# switch_1.net
KiCad netlist of a schematic drawn in Altium Designer
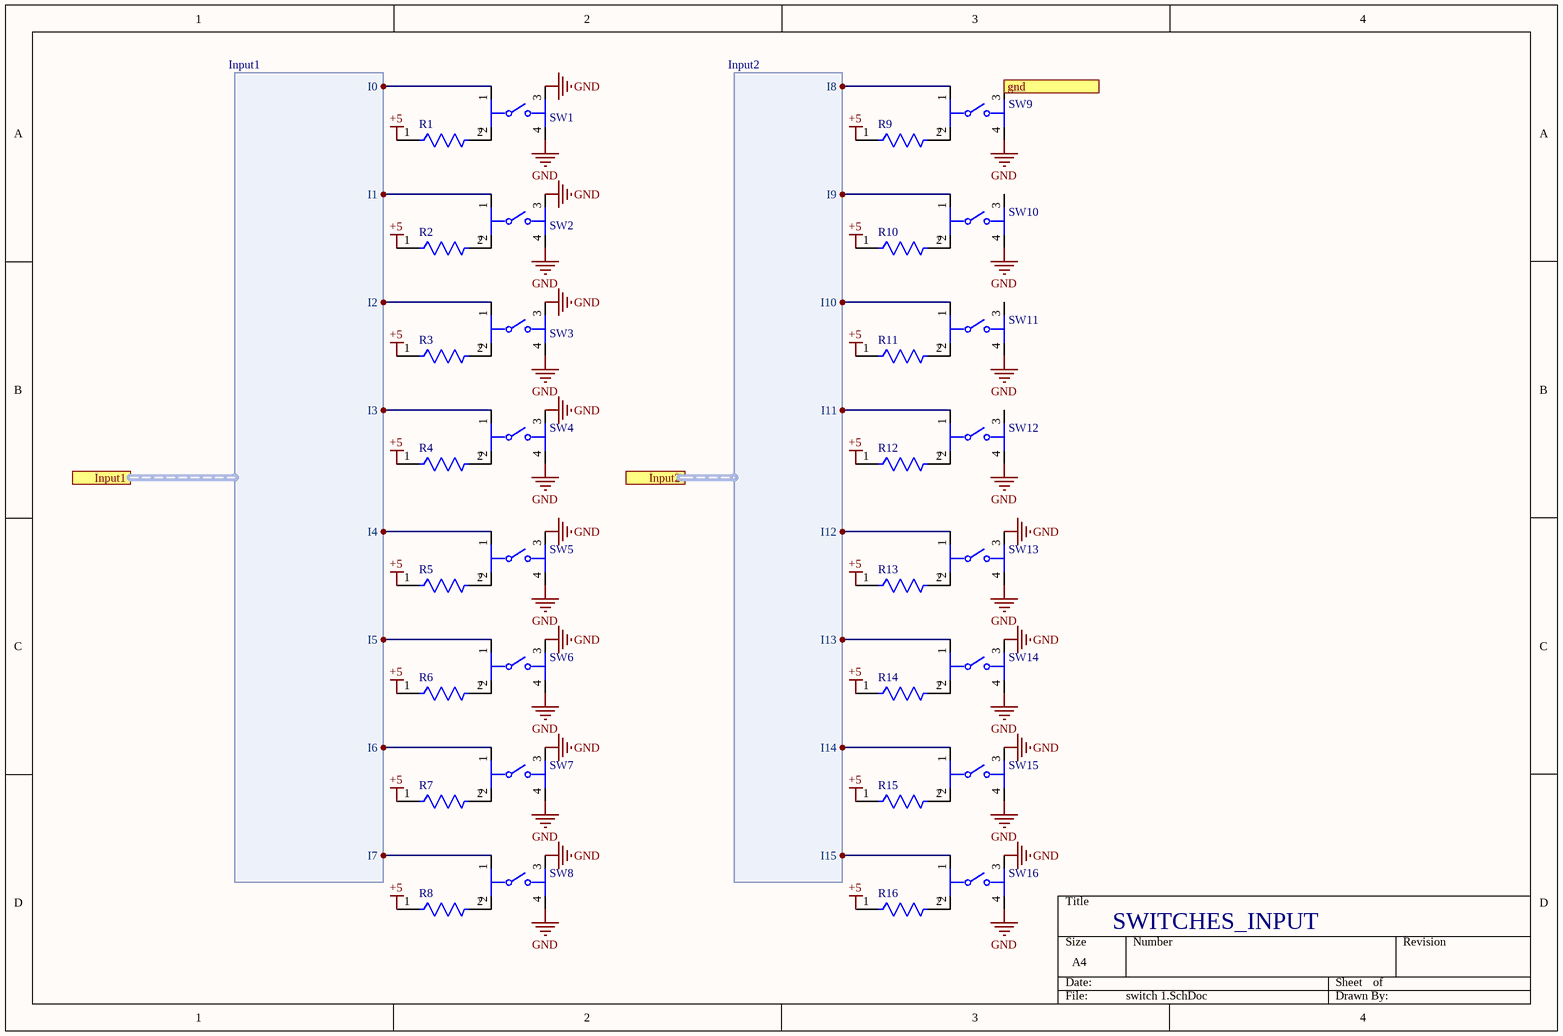
[diagram p0: switch 1.SchDoc]

(export (version "E")
  (design (tool "Eeschema 10.0.6"))
  (components
    (comp (ref "R1")
      (value "MRS25000C1001FCT00")
      (footprint "FP-MRS25-MFG")
      (description "RES 1K OHM 0.6W 1% AXIAL")
      (fields (field (name "TOLERANCE") "1%"))
      (libsource (lib "Altium Content Vault") (part "1029c3af85768c4190bb7ad29bc67b5"))
    )
    (comp (ref "R2")
      (value "MRS25000C1001FCT00")
      (footprint "FP-MRS25-MFG")
      (description "RES 1K OHM 0.6W 1% AXIAL")
      (fields (field (name "TOLERANCE") "1%"))
      (libsource (lib "Altium Content Vault") (part "1029c3af85768c4190bb7ad29bc67b5"))
    )
    (comp (ref "R3")
      (value "MRS25000C1001FCT00")
      (footprint "FP-MRS25-MFG")
      (description "RES 1K OHM 0.6W 1% AXIAL")
      (fields (field (name "TOLERANCE") "1%"))
      (libsource (lib "Altium Content Vault") (part "1029c3af85768c4190bb7ad29bc67b5"))
    )
    (comp (ref "R4")
      (value "MRS25000C1001FCT00")
      (footprint "FP-MRS25-MFG")
      (description "RES 1K OHM 0.6W 1% AXIAL")
      (fields (field (name "TOLERANCE") "1%"))
      (libsource (lib "Altium Content Vault") (part "1029c3af85768c4190bb7ad29bc67b5"))
    )
    (comp (ref "R5")
      (value "MRS25000C1001FCT00")
      (footprint "FP-MRS25-MFG")
      (description "RES 1K OHM 0.6W 1% AXIAL")
      (fields (field (name "TOLERANCE") "1%"))
      (libsource (lib "Altium Content Vault") (part "1029c3af85768c4190bb7ad29bc67b5"))
    )
    (comp (ref "R6")
      (value "MRS25000C1001FCT00")
      (footprint "FP-MRS25-MFG")
      (description "RES 1K OHM 0.6W 1% AXIAL")
      (fields (field (name "TOLERANCE") "1%"))
      (libsource (lib "Altium Content Vault") (part "1029c3af85768c4190bb7ad29bc67b5"))
    )
    (comp (ref "R7")
      (value "MRS25000C1001FCT00")
      (footprint "FP-MRS25-MFG")
      (description "RES 1K OHM 0.6W 1% AXIAL")
      (fields (field (name "TOLERANCE") "1%"))
      (libsource (lib "Altium Content Vault") (part "1029c3af85768c4190bb7ad29bc67b5"))
    )
    (comp (ref "R8")
      (value "MRS25000C1001FCT00")
      (footprint "FP-MRS25-MFG")
      (description "RES 1K OHM 0.6W 1% AXIAL")
      (fields (field (name "TOLERANCE") "1%"))
      (libsource (lib "Altium Content Vault") (part "1029c3af85768c4190bb7ad29bc67b5"))
    )
    (comp (ref "R9")
      (value "MRS25000C1001FCT00")
      (footprint "FP-MRS25-MFG")
      (description "RES 1K OHM 0.6W 1% AXIAL")
      (fields (field (name "TOLERANCE") "1%"))
      (libsource (lib "Altium Content Vault") (part "1029c3af85768c4190bb7ad29bc67b5"))
    )
    (comp (ref "R10")
      (value "MRS25000C1001FCT00")
      (footprint "FP-MRS25-MFG")
      (description "RES 1K OHM 0.6W 1% AXIAL")
      (fields (field (name "TOLERANCE") "1%"))
      (libsource (lib "Altium Content Vault") (part "1029c3af85768c4190bb7ad29bc67b5"))
    )
    (comp (ref "R11")
      (value "MRS25000C1001FCT00")
      (footprint "FP-MRS25-MFG")
      (description "RES 1K OHM 0.6W 1% AXIAL")
      (fields (field (name "TOLERANCE") "1%"))
      (libsource (lib "Altium Content Vault") (part "1029c3af85768c4190bb7ad29bc67b5"))
    )
    (comp (ref "R12")
      (value "MRS25000C1001FCT00")
      (footprint "FP-MRS25-MFG")
      (description "RES 1K OHM 0.6W 1% AXIAL")
      (fields (field (name "TOLERANCE") "1%"))
      (libsource (lib "Altium Content Vault") (part "1029c3af85768c4190bb7ad29bc67b5"))
    )
    (comp (ref "R13")
      (value "MRS25000C1001FCT00")
      (footprint "FP-MRS25-MFG")
      (description "RES 1K OHM 0.6W 1% AXIAL")
      (fields (field (name "TOLERANCE") "1%"))
      (libsource (lib "Altium Content Vault") (part "1029c3af85768c4190bb7ad29bc67b5"))
    )
    (comp (ref "R14")
      (value "MRS25000C1001FCT00")
      (footprint "FP-MRS25-MFG")
      (description "RES 1K OHM 0.6W 1% AXIAL")
      (fields (field (name "TOLERANCE") "1%"))
      (libsource (lib "Altium Content Vault") (part "1029c3af85768c4190bb7ad29bc67b5"))
    )
    (comp (ref "R15")
      (value "MRS25000C1001FCT00")
      (footprint "FP-MRS25-MFG")
      (description "RES 1K OHM 0.6W 1% AXIAL")
      (fields (field (name "TOLERANCE") "1%"))
      (libsource (lib "Altium Content Vault") (part "1029c3af85768c4190bb7ad29bc67b5"))
    )
    (comp (ref "R16")
      (value "MRS25000C1001FCT00")
      (footprint "FP-MRS25-MFG")
      (description "RES 1K OHM 0.6W 1% AXIAL")
      (fields (field (name "TOLERANCE") "1%"))
      (libsource (lib "Altium Content Vault") (part "1029c3af85768c4190bb7ad29bc67b5"))
    )
    (comp (ref "SW1")
      (value "1-1825910-5")
      (footprint "FP-1-1825910-5-MFG")
      (description "SWITCH TACTILE SPST-NO 0.05A 24V")
      (libsource (lib "Altium Content Vault") (part "b8895f3f4cefb76e1819d2863dba89b"))
    )
    (comp (ref "SW2")
      (value "1-1825910-5")
      (footprint "FP-1-1825910-5-MFG")
      (description "SWITCH TACTILE SPST-NO 0.05A 24V")
      (libsource (lib "Altium Content Vault") (part "b8895f3f4cefb76e1819d2863dba89b"))
    )
    (comp (ref "SW3")
      (value "1-1825910-5")
      (footprint "FP-1-1825910-5-MFG")
      (description "SWITCH TACTILE SPST-NO 0.05A 24V")
      (libsource (lib "Altium Content Vault") (part "b8895f3f4cefb76e1819d2863dba89b"))
    )
    (comp (ref "SW4")
      (value "1-1825910-5")
      (footprint "FP-1-1825910-5-MFG")
      (description "SWITCH TACTILE SPST-NO 0.05A 24V")
      (libsource (lib "Altium Content Vault") (part "b8895f3f4cefb76e1819d2863dba89b"))
    )
    (comp (ref "SW5")
      (value "1-1825910-5")
      (footprint "FP-1-1825910-5-MFG")
      (description "SWITCH TACTILE SPST-NO 0.05A 24V")
      (libsource (lib "Altium Content Vault") (part "b8895f3f4cefb76e1819d2863dba89b"))
    )
    (comp (ref "SW6")
      (value "1-1825910-5")
      (footprint "FP-1-1825910-5-MFG")
      (description "SWITCH TACTILE SPST-NO 0.05A 24V")
      (libsource (lib "Altium Content Vault") (part "b8895f3f4cefb76e1819d2863dba89b"))
    )
    (comp (ref "SW7")
      (value "1-1825910-5")
      (footprint "FP-1-1825910-5-MFG")
      (description "SWITCH TACTILE SPST-NO 0.05A 24V")
      (libsource (lib "Altium Content Vault") (part "b8895f3f4cefb76e1819d2863dba89b"))
    )
    (comp (ref "SW8")
      (value "1-1825910-5")
      (footprint "FP-1-1825910-5-MFG")
      (description "SWITCH TACTILE SPST-NO 0.05A 24V")
      (libsource (lib "Altium Content Vault") (part "b8895f3f4cefb76e1819d2863dba89b"))
    )
    (comp (ref "SW9")
      (value "1-1825910-5")
      (footprint "FP-1-1825910-5-MFG")
      (description "SWITCH TACTILE SPST-NO 0.05A 24V")
      (libsource (lib "Altium Content Vault") (part "b8895f3f4cefb76e1819d2863dba89b"))
    )
    (comp (ref "SW10")
      (value "1-1825910-5")
      (footprint "FP-1-1825910-5-MFG")
      (description "SWITCH TACTILE SPST-NO 0.05A 24V")
      (libsource (lib "Altium Content Vault") (part "b8895f3f4cefb76e1819d2863dba89b"))
    )
    (comp (ref "SW11")
      (value "1-1825910-5")
      (footprint "FP-1-1825910-5-MFG")
      (description "SWITCH TACTILE SPST-NO 0.05A 24V")
      (libsource (lib "Altium Content Vault") (part "b8895f3f4cefb76e1819d2863dba89b"))
    )
    (comp (ref "SW12")
      (value "1-1825910-5")
      (footprint "FP-1-1825910-5-MFG")
      (description "SWITCH TACTILE SPST-NO 0.05A 24V")
      (libsource (lib "Altium Content Vault") (part "b8895f3f4cefb76e1819d2863dba89b"))
    )
    (comp (ref "SW13")
      (value "1-1825910-5")
      (footprint "FP-1-1825910-5-MFG")
      (description "SWITCH TACTILE SPST-NO 0.05A 24V")
      (libsource (lib "Altium Content Vault") (part "b8895f3f4cefb76e1819d2863dba89b"))
    )
    (comp (ref "SW14")
      (value "1-1825910-5")
      (footprint "FP-1-1825910-5-MFG")
      (description "SWITCH TACTILE SPST-NO 0.05A 24V")
      (libsource (lib "Altium Content Vault") (part "b8895f3f4cefb76e1819d2863dba89b"))
    )
    (comp (ref "SW15")
      (value "1-1825910-5")
      (footprint "FP-1-1825910-5-MFG")
      (description "SWITCH TACTILE SPST-NO 0.05A 24V")
      (libsource (lib "Altium Content Vault") (part "b8895f3f4cefb76e1819d2863dba89b"))
    )
    (comp (ref "SW16")
      (value "1-1825910-5")
      (footprint "FP-1-1825910-5-MFG")
      (description "SWITCH TACTILE SPST-NO 0.05A 24V")
      (libsource (lib "Altium Content Vault") (part "b8895f3f4cefb76e1819d2863dba89b"))
    )
  )
  (nets
    (net (code "3") (name "+5") (class "Default")
      (node (ref "R1") (pin "1") (pinfunction "1_1") (pintype "passive"))
      (node (ref "R10") (pin "1") (pinfunction "1_1") (pintype "passive"))
      (node (ref "R11") (pin "1") (pinfunction "1_1") (pintype "passive"))
      (node (ref "R12") (pin "1") (pinfunction "1_1") (pintype "passive"))
      (node (ref "R13") (pin "1") (pinfunction "1_1") (pintype "passive"))
      (node (ref "R14") (pin "1") (pinfunction "1_1") (pintype "passive"))
      (node (ref "R15") (pin "1") (pinfunction "1_1") (pintype "passive"))
      (node (ref "R16") (pin "1") (pinfunction "1_1") (pintype "passive"))
      (node (ref "R2") (pin "1") (pinfunction "1_1") (pintype "passive"))
      (node (ref "R3") (pin "1") (pinfunction "1_1") (pintype "passive"))
      (node (ref "R4") (pin "1") (pinfunction "1_1") (pintype "passive"))
      (node (ref "R5") (pin "1") (pinfunction "1_1") (pintype "passive"))
      (node (ref "R6") (pin "1") (pinfunction "1_1") (pintype "passive"))
      (node (ref "R7") (pin "1") (pinfunction "1_1") (pintype "passive"))
      (node (ref "R8") (pin "1") (pinfunction "1_1") (pintype "passive"))
      (node (ref "R9") (pin "1") (pinfunction "1_1") (pintype "passive"))
    )
    (net (code "4") (name "/I0") (class "Default")
      (node (ref "SW1") (pin "1") (pinfunction "1_1") (pintype "passive"))
    )
    (net (code "5") (name "/I1") (class "Default")
      (node (ref "SW2") (pin "1") (pinfunction "1_1") (pintype "passive"))
    )
    (net (code "6") (name "/I2") (class "Default")
      (node (ref "SW3") (pin "1") (pinfunction "1_1") (pintype "passive"))
    )
    (net (code "7") (name "/I3") (class "Default")
      (node (ref "SW4") (pin "1") (pinfunction "1_1") (pintype "passive"))
    )
    (net (code "8") (name "/I4") (class "Default")
      (node (ref "SW5") (pin "1") (pinfunction "1_1") (pintype "passive"))
    )
    (net (code "9") (name "/I5") (class "Default")
      (node (ref "SW6") (pin "1") (pinfunction "1_1") (pintype "passive"))
    )
    (net (code "10") (name "/I6") (class "Default")
      (node (ref "SW7") (pin "1") (pinfunction "1_1") (pintype "passive"))
    )
    (net (code "11") (name "/I7") (class "Default")
      (node (ref "SW8") (pin "1") (pinfunction "1_1") (pintype "passive"))
    )
    (net (code "12") (name "/I8") (class "Default")
      (node (ref "SW9") (pin "1") (pinfunction "1_1") (pintype "passive"))
    )
    (net (code "13") (name "/I9") (class "Default")
      (node (ref "SW10") (pin "1") (pinfunction "1_1") (pintype "passive"))
    )
    (net (code "14") (name "/I10") (class "Default")
      (node (ref "SW11") (pin "1") (pinfunction "1_1") (pintype "passive"))
    )
    (net (code "15") (name "/I11") (class "Default")
      (node (ref "SW12") (pin "1") (pinfunction "1_1") (pintype "passive"))
    )
    (net (code "16") (name "/I12") (class "Default")
      (node (ref "SW13") (pin "1") (pinfunction "1_1") (pintype "passive"))
    )
    (net (code "17") (name "/I13") (class "Default")
      (node (ref "SW14") (pin "1") (pinfunction "1_1") (pintype "passive"))
    )
    (net (code "18") (name "/I14") (class "Default")
      (node (ref "SW15") (pin "1") (pinfunction "1_1") (pintype "passive"))
    )
    (net (code "19") (name "/I15") (class "Default")
      (node (ref "SW16") (pin "1") (pinfunction "1_1") (pintype "passive"))
    )
    (net (code "20") (name "/gnd") (class "Default")
      (node (ref "SW9") (pin "3") (pinfunction "3_3") (pintype "passive"))
    )
    (net (code "23") (name "GND") (class "Default")
      (node (ref "SW1") (pin "3") (pinfunction "3_3") (pintype "passive"))
      (node (ref "SW1") (pin "4") (pinfunction "4_4") (pintype "passive"))
      (node (ref "SW10") (pin "4") (pinfunction "4_4") (pintype "passive"))
      (node (ref "SW11") (pin "4") (pinfunction "4_4") (pintype "passive"))
      (node (ref "SW12") (pin "4") (pinfunction "4_4") (pintype "passive"))
      (node (ref "SW13") (pin "3") (pinfunction "3_3") (pintype "passive"))
      (node (ref "SW13") (pin "4") (pinfunction "4_4") (pintype "passive"))
      (node (ref "SW14") (pin "3") (pinfunction "3_3") (pintype "passive"))
      (node (ref "SW14") (pin "4") (pinfunction "4_4") (pintype "passive"))
      (node (ref "SW15") (pin "3") (pinfunction "3_3") (pintype "passive"))
      (node (ref "SW15") (pin "4") (pinfunction "4_4") (pintype "passive"))
      (node (ref "SW16") (pin "3") (pinfunction "3_3") (pintype "passive"))
      (node (ref "SW16") (pin "4") (pinfunction "4_4") (pintype "passive"))
      (node (ref "SW2") (pin "3") (pinfunction "3_3") (pintype "passive"))
      (node (ref "SW2") (pin "4") (pinfunction "4_4") (pintype "passive"))
      (node (ref "SW3") (pin "3") (pinfunction "3_3") (pintype "passive"))
      (node (ref "SW3") (pin "4") (pinfunction "4_4") (pintype "passive"))
      (node (ref "SW4") (pin "3") (pinfunction "3_3") (pintype "passive"))
      (node (ref "SW4") (pin "4") (pinfunction "4_4") (pintype "passive"))
      (node (ref "SW5") (pin "3") (pinfunction "3_3") (pintype "passive"))
      (node (ref "SW5") (pin "4") (pinfunction "4_4") (pintype "passive"))
      (node (ref "SW6") (pin "3") (pinfunction "3_3") (pintype "passive"))
      (node (ref "SW6") (pin "4") (pinfunction "4_4") (pintype "passive"))
      (node (ref "SW7") (pin "3") (pinfunction "3_3") (pintype "passive"))
      (node (ref "SW7") (pin "4") (pinfunction "4_4") (pintype "passive"))
      (node (ref "SW8") (pin "3") (pinfunction "3_3") (pintype "passive"))
      (node (ref "SW8") (pin "4") (pinfunction "4_4") (pintype "passive"))
      (node (ref "SW9") (pin "4") (pinfunction "4_4") (pintype "passive"))
    )
    (net (code "24") (name "Net-(R1-Pad2)") (class "Default")
      (node (ref "R1") (pin "2") (pinfunction "2_2") (pintype "passive"))
      (node (ref "SW1") (pin "2") (pinfunction "2_2") (pintype "passive"))
    )
    (net (code "25") (name "Net-(R2-Pad2)") (class "Default")
      (node (ref "R2") (pin "2") (pinfunction "2_2") (pintype "passive"))
      (node (ref "SW2") (pin "2") (pinfunction "2_2") (pintype "passive"))
    )
    (net (code "26") (name "Net-(R3-Pad2)") (class "Default")
      (node (ref "R3") (pin "2") (pinfunction "2_2") (pintype "passive"))
      (node (ref "SW3") (pin "2") (pinfunction "2_2") (pintype "passive"))
    )
    (net (code "27") (name "Net-(R4-Pad2)") (class "Default")
      (node (ref "R4") (pin "2") (pinfunction "2_2") (pintype "passive"))
      (node (ref "SW4") (pin "2") (pinfunction "2_2") (pintype "passive"))
    )
    (net (code "28") (name "Net-(R5-Pad2)") (class "Default")
      (node (ref "R5") (pin "2") (pinfunction "2_2") (pintype "passive"))
      (node (ref "SW5") (pin "2") (pinfunction "2_2") (pintype "passive"))
    )
    (net (code "29") (name "Net-(R6-Pad2)") (class "Default")
      (node (ref "R6") (pin "2") (pinfunction "2_2") (pintype "passive"))
      (node (ref "SW6") (pin "2") (pinfunction "2_2") (pintype "passive"))
    )
    (net (code "30") (name "Net-(R7-Pad2)") (class "Default")
      (node (ref "R7") (pin "2") (pinfunction "2_2") (pintype "passive"))
      (node (ref "SW7") (pin "2") (pinfunction "2_2") (pintype "passive"))
    )
    (net (code "31") (name "Net-(R8-Pad2)") (class "Default")
      (node (ref "R8") (pin "2") (pinfunction "2_2") (pintype "passive"))
      (node (ref "SW8") (pin "2") (pinfunction "2_2") (pintype "passive"))
    )
    (net (code "32") (name "Net-(R9-Pad2)") (class "Default")
      (node (ref "R9") (pin "2") (pinfunction "2_2") (pintype "passive"))
      (node (ref "SW9") (pin "2") (pinfunction "2_2") (pintype "passive"))
    )
    (net (code "33") (name "Net-(R10-Pad2)") (class "Default")
      (node (ref "R10") (pin "2") (pinfunction "2_2") (pintype "passive"))
      (node (ref "SW10") (pin "2") (pinfunction "2_2") (pintype "passive"))
    )
    (net (code "34") (name "Net-(R11-Pad2)") (class "Default")
      (node (ref "R11") (pin "2") (pinfunction "2_2") (pintype "passive"))
      (node (ref "SW11") (pin "2") (pinfunction "2_2") (pintype "passive"))
    )
    (net (code "35") (name "Net-(R12-Pad2)") (class "Default")
      (node (ref "R12") (pin "2") (pinfunction "2_2") (pintype "passive"))
      (node (ref "SW12") (pin "2") (pinfunction "2_2") (pintype "passive"))
    )
    (net (code "36") (name "Net-(R13-Pad2)") (class "Default")
      (node (ref "R13") (pin "2") (pinfunction "2_2") (pintype "passive"))
      (node (ref "SW13") (pin "2") (pinfunction "2_2") (pintype "passive"))
    )
    (net (code "37") (name "Net-(R14-Pad2)") (class "Default")
      (node (ref "R14") (pin "2") (pinfunction "2_2") (pintype "passive"))
      (node (ref "SW14") (pin "2") (pinfunction "2_2") (pintype "passive"))
    )
    (net (code "38") (name "Net-(R15-Pad2)") (class "Default")
      (node (ref "R15") (pin "2") (pinfunction "2_2") (pintype "passive"))
      (node (ref "SW15") (pin "2") (pinfunction "2_2") (pintype "passive"))
    )
    (net (code "39") (name "Net-(R16-Pad2)") (class "Default")
      (node (ref "R16") (pin "2") (pinfunction "2_2") (pintype "passive"))
      (node (ref "SW16") (pin "2") (pinfunction "2_2") (pintype "passive"))
    )
    (net (code "40") (name "unconnected-(SW10-Pad3)") (class "Default")
      (node (ref "SW10") (pin "3") (pinfunction "3_3") (pintype "passive"))
    )
    (net (code "41") (name "unconnected-(SW11-Pad3)") (class "Default")
      (node (ref "SW11") (pin "3") (pinfunction "3_3") (pintype "passive"))
    )
    (net (code "42") (name "unconnected-(SW12-Pad3)") (class "Default")
      (node (ref "SW12") (pin "3") (pinfunction "3_3") (pintype "passive"))
    )
  )
)
